# line_sensor_t.net
KiCad netlist of a schematic drawn in EAGLE
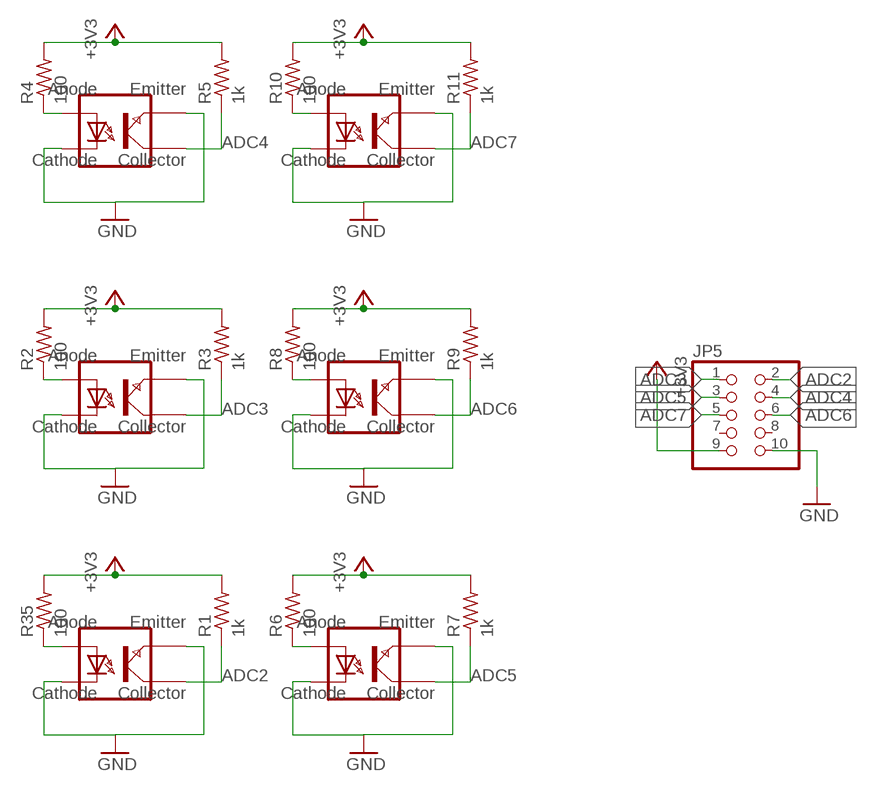
[diagram p0: schematic, sheet 1]

(export (version "E")
  (design (tool "Eeschema 10.0.6"))
  (components
    (comp (ref "JP5")
      (value "PINHD-2X5/90")
      (footprint "eagle-import:2X05_90")
      (libsource (lib "eagle-import") (part "PINHD-2X5/90"))
    )
    (comp (ref "R1")
      (value "1k")
      (footprint "eagle-import:M2012")
      (libsource (lib "eagle-import") (part "R-US_M2012"))
    )
    (comp (ref "R2")
      (value "100")
      (footprint "eagle-import:M2012")
      (libsource (lib "eagle-import") (part "R-US_M2012"))
    )
    (comp (ref "R3")
      (value "1k")
      (footprint "eagle-import:M2012")
      (libsource (lib "eagle-import") (part "R-US_M2012"))
    )
    (comp (ref "R4")
      (value "100")
      (footprint "eagle-import:M2012")
      (libsource (lib "eagle-import") (part "R-US_M2012"))
    )
    (comp (ref "R5")
      (value "1k")
      (footprint "eagle-import:M2012")
      (libsource (lib "eagle-import") (part "R-US_M2012"))
    )
    (comp (ref "R6")
      (value "100")
      (footprint "eagle-import:M2012")
      (libsource (lib "eagle-import") (part "R-US_M2012"))
    )
    (comp (ref "R7")
      (value "1k")
      (footprint "eagle-import:M2012")
      (libsource (lib "eagle-import") (part "R-US_M2012"))
    )
    (comp (ref "R8")
      (value "100")
      (footprint "eagle-import:M2012")
      (libsource (lib "eagle-import") (part "R-US_M2012"))
    )
    (comp (ref "R9")
      (value "1k")
      (footprint "eagle-import:M2012")
      (libsource (lib "eagle-import") (part "R-US_M2012"))
    )
    (comp (ref "R10")
      (value "100")
      (footprint "eagle-import:M2012")
      (libsource (lib "eagle-import") (part "R-US_M2012"))
    )
    (comp (ref "R11")
      (value "1k")
      (footprint "eagle-import:M2012")
      (libsource (lib "eagle-import") (part "R-US_M2012"))
    )
    (comp (ref "R35")
      (value "100")
      (footprint "eagle-import:M2012")
      (libsource (lib "eagle-import") (part "R-US_M2012"))
    )
    (comp (ref "U$1")
      (value "LBR-127HLD")
      (footprint "eagle-import:LBR-127HLD")
      (libsource (lib "eagle-import") (part "LBR-127HLD"))
    )
    (comp (ref "U$2")
      (value "LBR-127HLD")
      (footprint "eagle-import:LBR-127HLD")
      (libsource (lib "eagle-import") (part "LBR-127HLD"))
    )
    (comp (ref "U$3")
      (value "LBR-127HLD")
      (footprint "eagle-import:LBR-127HLD")
      (libsource (lib "eagle-import") (part "LBR-127HLD"))
    )
    (comp (ref "U$4")
      (value "LBR-127HLD")
      (footprint "eagle-import:LBR-127HLD")
      (libsource (lib "eagle-import") (part "LBR-127HLD"))
    )
    (comp (ref "U$5")
      (value "LBR-127HLD")
      (footprint "eagle-import:LBR-127HLD")
      (libsource (lib "eagle-import") (part "LBR-127HLD"))
    )
    (comp (ref "U$6")
      (value "LBR-127HLD")
      (footprint "eagle-import:LBR-127HLD")
      (libsource (lib "eagle-import") (part "LBR-127HLD"))
    )
  )
  (nets
    (net (code "1") (name "+3V3") (class "Default")
      (node (ref "JP5") (pin "9") (pinfunction "9_9") (pintype "passive"))
      (node (ref "R1") (pin "2") (pinfunction "2_2") (pintype "passive"))
      (node (ref "R10") (pin "2") (pinfunction "2_2") (pintype "passive"))
      (node (ref "R11") (pin "2") (pinfunction "2_2") (pintype "passive"))
      (node (ref "R2") (pin "2") (pinfunction "2_2") (pintype "passive"))
      (node (ref "R3") (pin "2") (pinfunction "2_2") (pintype "passive"))
      (node (ref "R35") (pin "2") (pinfunction "2_2") (pintype "passive"))
      (node (ref "R4") (pin "2") (pinfunction "2_2") (pintype "passive"))
      (node (ref "R5") (pin "2") (pinfunction "2_2") (pintype "passive"))
      (node (ref "R6") (pin "2") (pinfunction "2_2") (pintype "passive"))
      (node (ref "R7") (pin "2") (pinfunction "2_2") (pintype "passive"))
      (node (ref "R8") (pin "2") (pinfunction "2_2") (pintype "passive"))
      (node (ref "R9") (pin "2") (pinfunction "2_2") (pintype "passive"))
    )
    (net (code "2") (name "ADC2") (class "Default")
      (node (ref "JP5") (pin "2") (pinfunction "2_2") (pintype "passive"))
      (node (ref "R1") (pin "1") (pinfunction "1_1") (pintype "passive"))
      (node (ref "U$1") (pin "COLLECTOR") (pinfunction "COLLECTOR_COLLECTOR") (pintype "bidirectional"))
    )
    (net (code "3") (name "ADC3") (class "Default")
      (node (ref "JP5") (pin "1") (pinfunction "1_1") (pintype "passive"))
      (node (ref "R3") (pin "1") (pinfunction "1_1") (pintype "passive"))
      (node (ref "U$2") (pin "COLLECTOR") (pinfunction "COLLECTOR_COLLECTOR") (pintype "bidirectional"))
    )
    (net (code "4") (name "ADC4") (class "Default")
      (node (ref "JP5") (pin "4") (pinfunction "4_4") (pintype "passive"))
      (node (ref "R5") (pin "1") (pinfunction "1_1") (pintype "passive"))
      (node (ref "U$3") (pin "COLLECTOR") (pinfunction "COLLECTOR_COLLECTOR") (pintype "bidirectional"))
    )
    (net (code "5") (name "ADC5") (class "Default")
      (node (ref "JP5") (pin "3") (pinfunction "3_3") (pintype "passive"))
      (node (ref "R7") (pin "1") (pinfunction "1_1") (pintype "passive"))
      (node (ref "U$4") (pin "COLLECTOR") (pinfunction "COLLECTOR_COLLECTOR") (pintype "bidirectional"))
    )
    (net (code "6") (name "ADC6") (class "Default")
      (node (ref "JP5") (pin "6") (pinfunction "6_6") (pintype "passive"))
      (node (ref "R9") (pin "1") (pinfunction "1_1") (pintype "passive"))
      (node (ref "U$5") (pin "COLLECTOR") (pinfunction "COLLECTOR_COLLECTOR") (pintype "bidirectional"))
    )
    (net (code "7") (name "ADC7") (class "Default")
      (node (ref "JP5") (pin "5") (pinfunction "5_5") (pintype "passive"))
      (node (ref "R11") (pin "1") (pinfunction "1_1") (pintype "passive"))
      (node (ref "U$6") (pin "COLLECTOR") (pinfunction "COLLECTOR_COLLECTOR") (pintype "bidirectional"))
    )
    (net (code "8") (name "GND") (class "Default")
      (node (ref "JP5") (pin "10") (pinfunction "10_10") (pintype "passive"))
      (node (ref "U$1") (pin "CATHODE") (pinfunction "CATHODE_CATHODE") (pintype "bidirectional"))
      (node (ref "U$1") (pin "EMITTER") (pinfunction "EMITTER_EMITTER") (pintype "bidirectional"))
      (node (ref "U$2") (pin "CATHODE") (pinfunction "CATHODE_CATHODE") (pintype "bidirectional"))
      (node (ref "U$2") (pin "EMITTER") (pinfunction "EMITTER_EMITTER") (pintype "bidirectional"))
      (node (ref "U$3") (pin "CATHODE") (pinfunction "CATHODE_CATHODE") (pintype "bidirectional"))
      (node (ref "U$3") (pin "EMITTER") (pinfunction "EMITTER_EMITTER") (pintype "bidirectional"))
      (node (ref "U$4") (pin "CATHODE") (pinfunction "CATHODE_CATHODE") (pintype "bidirectional"))
      (node (ref "U$4") (pin "EMITTER") (pinfunction "EMITTER_EMITTER") (pintype "bidirectional"))
      (node (ref "U$5") (pin "CATHODE") (pinfunction "CATHODE_CATHODE") (pintype "bidirectional"))
      (node (ref "U$5") (pin "EMITTER") (pinfunction "EMITTER_EMITTER") (pintype "bidirectional"))
      (node (ref "U$6") (pin "CATHODE") (pinfunction "CATHODE_CATHODE") (pintype "bidirectional"))
      (node (ref "U$6") (pin "EMITTER") (pinfunction "EMITTER_EMITTER") (pintype "bidirectional"))
    )
    (net (code "9") (name "Net-(R2-Pad1)") (class "Default")
      (node (ref "R2") (pin "1") (pinfunction "1_1") (pintype "passive"))
      (node (ref "U$2") (pin "ANODE") (pinfunction "ANODE_ANODE") (pintype "bidirectional"))
    )
    (net (code "10") (name "Net-(R4-Pad1)") (class "Default")
      (node (ref "R4") (pin "1") (pinfunction "1_1") (pintype "passive"))
      (node (ref "U$3") (pin "ANODE") (pinfunction "ANODE_ANODE") (pintype "bidirectional"))
    )
    (net (code "11") (name "Net-(R6-Pad1)") (class "Default")
      (node (ref "R6") (pin "1") (pinfunction "1_1") (pintype "passive"))
      (node (ref "U$4") (pin "ANODE") (pinfunction "ANODE_ANODE") (pintype "bidirectional"))
    )
    (net (code "12") (name "Net-(R8-Pad1)") (class "Default")
      (node (ref "R8") (pin "1") (pinfunction "1_1") (pintype "passive"))
      (node (ref "U$5") (pin "ANODE") (pinfunction "ANODE_ANODE") (pintype "bidirectional"))
    )
    (net (code "13") (name "Net-(R10-Pad1)") (class "Default")
      (node (ref "R10") (pin "1") (pinfunction "1_1") (pintype "passive"))
      (node (ref "U$6") (pin "ANODE") (pinfunction "ANODE_ANODE") (pintype "bidirectional"))
    )
    (net (code "14") (name "Net-(R35-Pad1)") (class "Default")
      (node (ref "R35") (pin "1") (pinfunction "1_1") (pintype "passive"))
      (node (ref "U$1") (pin "ANODE") (pinfunction "ANODE_ANODE") (pintype "bidirectional"))
    )
    (net (code "15") (name "unconnected-(JP5-Pad7)") (class "Default")
      (node (ref "JP5") (pin "7") (pinfunction "7_7") (pintype "passive"))
    )
    (net (code "16") (name "unconnected-(JP5-Pad8)") (class "Default")
      (node (ref "JP5") (pin "8") (pinfunction "8_8") (pintype "passive"))
    )
  )
)
